# 2228_Emetteur_Systeme.net
KiCad netlist of a schematic drawn in Altium Designer
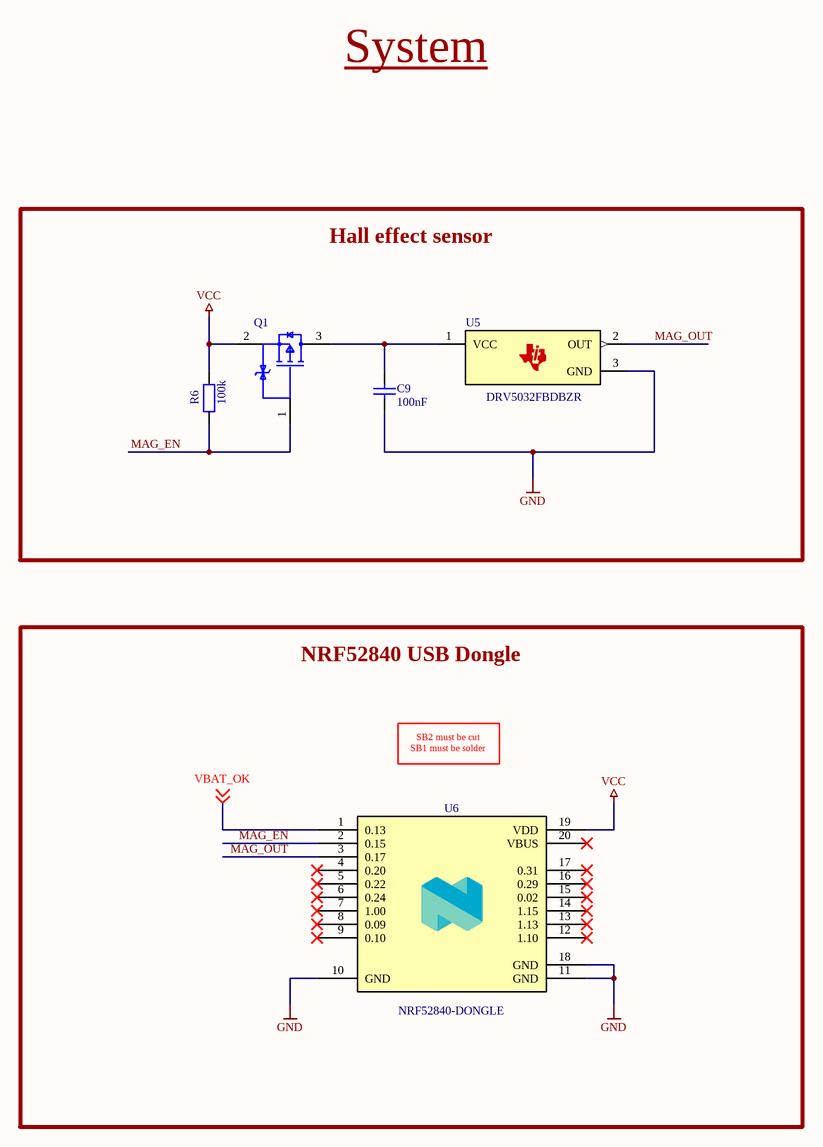
[diagram p0: 2228_Emetteur_Systeme.SchDoc]

(export (version "E")
  (design (tool "Eeschema 10.0.6"))
  (components
    (comp (ref "C9")
      (value "100nF")
      (footprint "CAP_0805")
      (description "Capacitor")
      (fields (field (name "Comment") "CAP_SMD"))
      (libsource (lib "2228_AlarmeFenetre_Symbols") (part "CAP_SMD"))
    )
    (comp (ref "Q1")
      (value "RZM001P02T2L")
      (footprint "FP-VMT3-MFG")
      (description "MOSFET P-CH 20V 0.1A VMT3")
      (fields
        (field (name "OCTOPART") "https://octopart.com/rzm001p02t2l-rohm-29677415")
        (field (name "MANUFACTURER") "Rohm")
      )
      (libsource (lib "Altium Content Vault") (part "2b2cac828553558a1ef0da1d67e22de"))
    )
    (comp (ref "R6")
      (value "100k")
      (footprint "RES_0805")
      (fields (field (name "Comment") "RES_SMD"))
      (libsource (lib "2228_AlarmeFenetre_Symbols") (part "RES_SMD"))
    )
    (comp (ref "U5")
      (value "DRV5032FBDBZR")
      (footprint "2228_AlarmeFenetre_Footprints:SOT95P237X112-3N")
      (fields (field (name "MANUFACTURER") "Texas Instruments"))
      (libsource (lib "2228_AlarmeFenetre_Symbols") (part "DRV5032FBDBZR"))
    )
    (comp (ref "U6")
      (value "NRF52840-DONGLE")
      (footprint "NRF52840_DONGLE")
      (fields (field (name "MANUFACTURER") "Nordic Semiconductor"))
      (libsource (lib "2228_AlarmeFenetre_Symbols") (part "NRF52840-DONGLE"))
    )
  )
  (nets
    (net (code "1") (name "/MAG_EN") (class "Default")
      (node (ref "Q1") (pin "1") (pinfunction "Gate_1") (pintype "passive"))
      (node (ref "R6") (pin "1") (pinfunction "1_1") (pintype "passive"))
      (node (ref "U6") (pin "2") (pinfunction "0.15_2") (pintype "passive"))
    )
    (net (code "2") (name "/MAG_OUT") (class "Default")
      (node (ref "U5") (pin "2") (pinfunction "OUT_2") (pintype "output"))
      (node (ref "U6") (pin "3") (pinfunction "0.17_3") (pintype "passive"))
    )
    (net (code "3") (name "GND") (class "Default")
      (node (ref "C9") (pin "1") (pinfunction "1_1") (pintype "passive"))
      (node (ref "U5") (pin "3") (pinfunction "GND_3") (pintype "power_in"))
      (node (ref "U6") (pin "10") (pinfunction "GND_10") (pintype "passive"))
      (node (ref "U6") (pin "11") (pinfunction "GND_11") (pintype "passive"))
      (node (ref "U6") (pin "18") (pinfunction "GND_18") (pintype "passive"))
    )
    (net (code "4") (name "Net-(Q1-Drain)") (class "Default")
      (node (ref "C9") (pin "2") (pinfunction "2_2") (pintype "passive"))
      (node (ref "Q1") (pin "3") (pinfunction "Drain_3") (pintype "passive"))
      (node (ref "U5") (pin "1") (pinfunction "VCC_1") (pintype "power_in"))
    )
    (net (code "5") (name "VBAT_OK") (class "Default")
      (node (ref "U6") (pin "1") (pinfunction "0.13_1") (pintype "passive"))
    )
    (net (code "6") (name "VCC") (class "Default")
      (node (ref "Q1") (pin "2") (pinfunction "Source_2") (pintype "passive"))
      (node (ref "R6") (pin "2") (pinfunction "2_2") (pintype "passive"))
      (node (ref "U6") (pin "19") (pinfunction "VDD_19") (pintype "passive"))
    )
    (net (code "7") (name "unconnected-(U6-0.02-Pad15)") (class "Default")
      (node (ref "U6") (pin "15") (pinfunction "0.02_15") (pintype "passive+no_connect"))
    )
    (net (code "8") (name "unconnected-(U6-0.09-Pad8)") (class "Default")
      (node (ref "U6") (pin "8") (pinfunction "0.09_8") (pintype "passive+no_connect"))
    )
    (net (code "9") (name "unconnected-(U6-0.10-Pad9)") (class "Default")
      (node (ref "U6") (pin "9") (pinfunction "0.10_9") (pintype "passive+no_connect"))
    )
    (net (code "10") (name "unconnected-(U6-0.20-Pad4)") (class "Default")
      (node (ref "U6") (pin "4") (pinfunction "0.20_4") (pintype "passive+no_connect"))
    )
    (net (code "11") (name "unconnected-(U6-0.22-Pad5)") (class "Default")
      (node (ref "U6") (pin "5") (pinfunction "0.22_5") (pintype "passive+no_connect"))
    )
    (net (code "12") (name "unconnected-(U6-0.24-Pad6)") (class "Default")
      (node (ref "U6") (pin "6") (pinfunction "0.24_6") (pintype "passive+no_connect"))
    )
    (net (code "13") (name "unconnected-(U6-0.29-Pad16)") (class "Default")
      (node (ref "U6") (pin "16") (pinfunction "0.29_16") (pintype "passive+no_connect"))
    )
    (net (code "14") (name "unconnected-(U6-0.31-Pad17)") (class "Default")
      (node (ref "U6") (pin "17") (pinfunction "0.31_17") (pintype "passive+no_connect"))
    )
    (net (code "15") (name "unconnected-(U6-1.00-Pad7)") (class "Default")
      (node (ref "U6") (pin "7") (pinfunction "1.00_7") (pintype "passive+no_connect"))
    )
    (net (code "16") (name "unconnected-(U6-1.10-Pad12)") (class "Default")
      (node (ref "U6") (pin "12") (pinfunction "1.10_12") (pintype "passive+no_connect"))
    )
    (net (code "17") (name "unconnected-(U6-1.13-Pad13)") (class "Default")
      (node (ref "U6") (pin "13") (pinfunction "1.13_13") (pintype "passive+no_connect"))
    )
    (net (code "18") (name "unconnected-(U6-1.15-Pad14)") (class "Default")
      (node (ref "U6") (pin "14") (pinfunction "1.15_14") (pintype "passive+no_connect"))
    )
    (net (code "19") (name "unconnected-(U6-VBUS-Pad20)") (class "Default")
      (node (ref "U6") (pin "20") (pinfunction "VBUS_20") (pintype "passive+no_connect"))
    )
  )
)
